# sumpower.net
KiCad netlist of a schematic drawn in Altium Designer
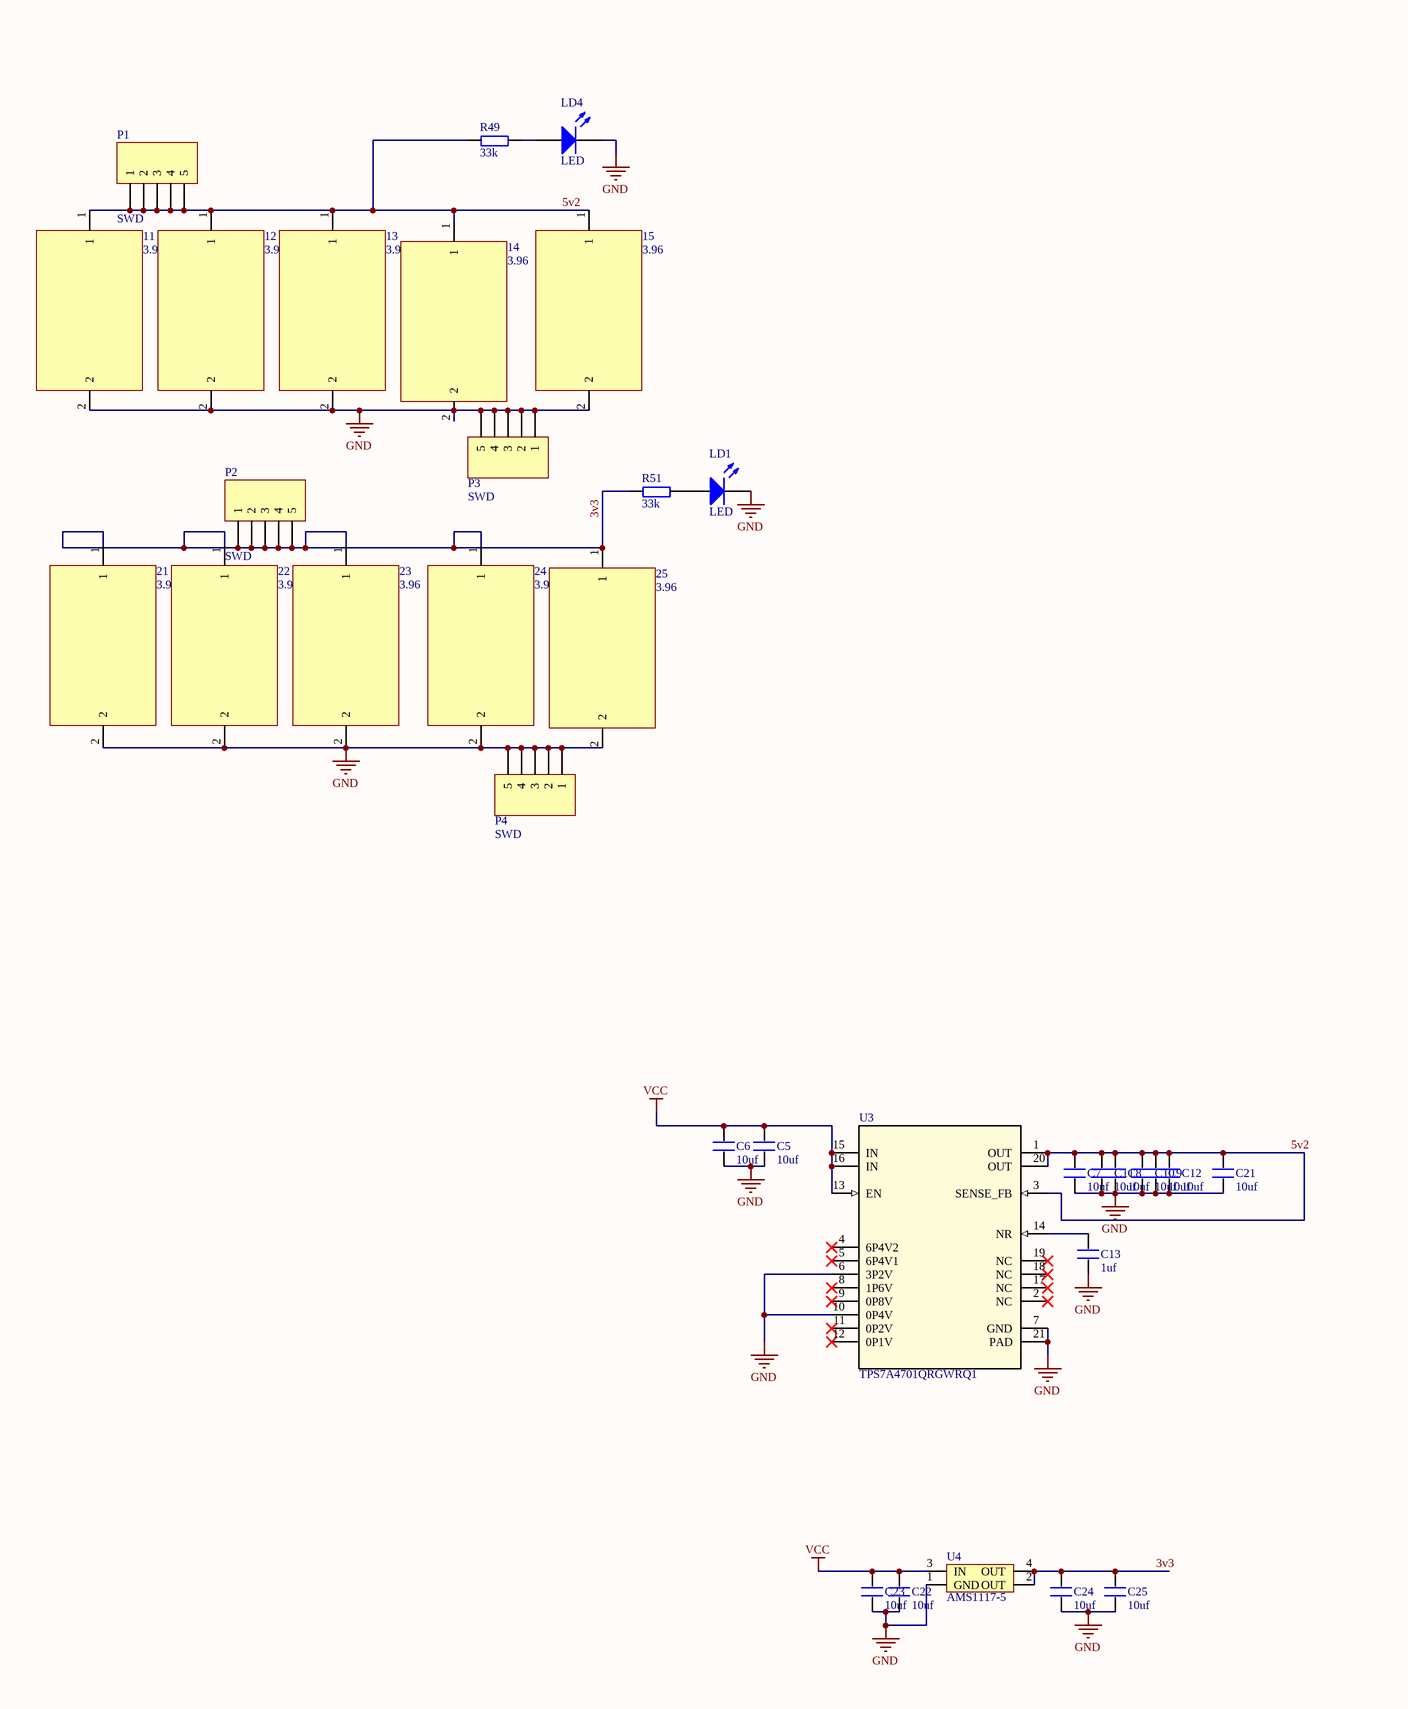
[diagram p0: sumpower.SchDoc, left]
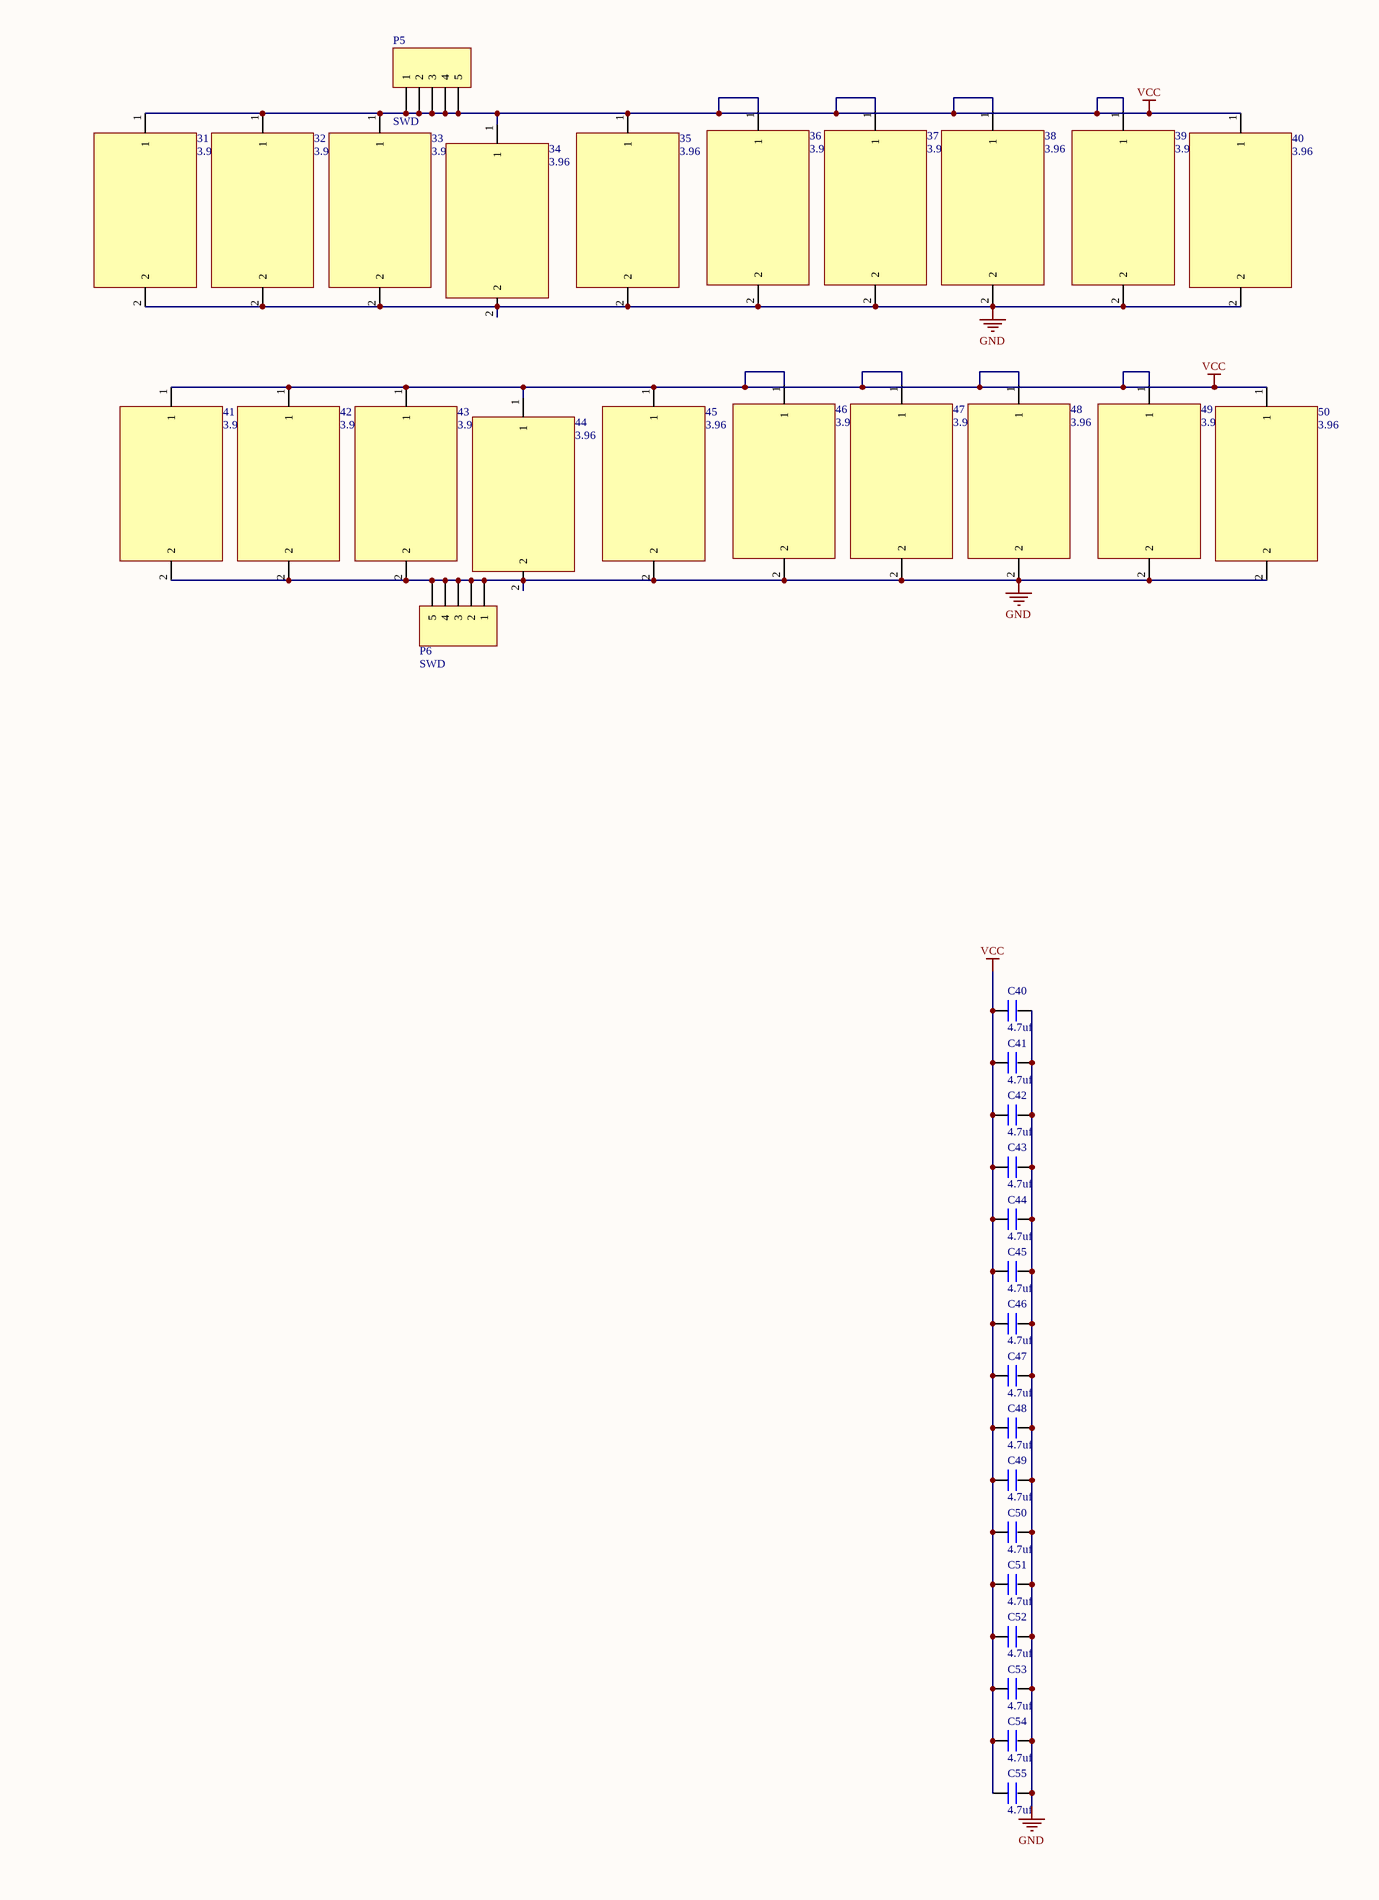
[diagram p1: sumpower.SchDoc, right]

(export (version "E")
  (design (tool "Eeschema 10.0.6"))
  (components
    (comp (ref "11") (value "3.96") (footprint "3.96") (libsource (lib "MYLIB") (part "3.96")))
    (comp (ref "12") (value "3.96") (footprint "3.96") (libsource (lib "MYLIB") (part "3.96")))
    (comp (ref "13") (value "3.96") (footprint "3.96") (libsource (lib "MYLIB") (part "3.96")))
    (comp (ref "14") (value "3.96") (footprint "3.96") (libsource (lib "MYLIB") (part "3.96")))
    (comp (ref "15") (value "3.96") (footprint "3.96") (libsource (lib "MYLIB") (part "3.96")))
    (comp (ref "21") (value "3.96") (footprint "3.96") (libsource (lib "MYLIB") (part "3.96")))
    (comp (ref "22") (value "3.96") (footprint "3.96") (libsource (lib "MYLIB") (part "3.96")))
    (comp (ref "23") (value "3.96") (footprint "3.96") (libsource (lib "MYLIB") (part "3.96")))
    (comp (ref "24") (value "3.96") (footprint "3.96") (libsource (lib "MYLIB") (part "3.96")))
    (comp (ref "25") (value "3.96") (footprint "3.96") (libsource (lib "MYLIB") (part "3.96")))
    (comp (ref "31") (value "3.96") (footprint "3.96") (libsource (lib "MYLIB") (part "3.96")))
    (comp (ref "32") (value "3.96") (footprint "3.96") (libsource (lib "MYLIB") (part "3.96")))
    (comp (ref "33") (value "3.96") (footprint "3.96") (libsource (lib "MYLIB") (part "3.96")))
    (comp (ref "34") (value "3.96") (footprint "3.96") (libsource (lib "MYLIB") (part "3.96")))
    (comp (ref "35") (value "3.96") (footprint "3.96") (libsource (lib "MYLIB") (part "3.96")))
    (comp (ref "36") (value "3.96") (footprint "3.96") (libsource (lib "MYLIB") (part "3.96")))
    (comp (ref "37") (value "3.96") (footprint "3.96") (libsource (lib "MYLIB") (part "3.96")))
    (comp (ref "38") (value "3.96") (footprint "3.96") (libsource (lib "MYLIB") (part "3.96")))
    (comp (ref "39") (value "3.96") (footprint "3.96") (libsource (lib "MYLIB") (part "3.96")))
    (comp (ref "40") (value "3.96") (footprint "3.96") (libsource (lib "MYLIB") (part "3.96")))
    (comp (ref "41") (value "3.96") (footprint "3.96") (libsource (lib "MYLIB") (part "3.96")))
    (comp (ref "42") (value "3.96") (footprint "3.96") (libsource (lib "MYLIB") (part "3.96")))
    (comp (ref "43") (value "3.96") (footprint "3.96") (libsource (lib "MYLIB") (part "3.96")))
    (comp (ref "44") (value "3.96") (footprint "3.96") (libsource (lib "MYLIB") (part "3.96")))
    (comp (ref "45") (value "3.96") (footprint "3.96") (libsource (lib "MYLIB") (part "3.96")))
    (comp (ref "46") (value "3.96") (footprint "3.96") (libsource (lib "MYLIB") (part "3.96")))
    (comp (ref "47") (value "3.96") (footprint "3.96") (libsource (lib "MYLIB") (part "3.96")))
    (comp (ref "48") (value "3.96") (footprint "3.96") (libsource (lib "MYLIB") (part "3.96")))
    (comp (ref "49") (value "3.96") (footprint "3.96") (libsource (lib "MYLIB") (part "3.96")))
    (comp (ref "50") (value "3.96") (footprint "3.96") (libsource (lib "MYLIB") (part "3.96")))
    (comp (ref "C5")
      (value "10uf")
      (footprint "0603C")
      (description "Capacitor")
      (libsource (lib "MYLIB") (part "C"))
    )
    (comp (ref "C6")
      (value "10uf")
      (footprint "0603C")
      (description "Capacitor")
      (libsource (lib "MYLIB") (part "C"))
    )
    (comp (ref "C7")
      (value "10uf")
      (footprint "0603C")
      (description "Capacitor")
      (libsource (lib "MYLIB") (part "C"))
    )
    (comp (ref "C8")
      (value "10uf")
      (footprint "0603C")
      (description "Capacitor")
      (libsource (lib "MYLIB") (part "C"))
    )
    (comp (ref "C9")
      (value "10uf")
      (footprint "0603C")
      (description "Capacitor")
      (libsource (lib "MYLIB") (part "C"))
    )
    (comp (ref "C10")
      (value "10uf")
      (footprint "0603C")
      (description "Capacitor")
      (libsource (lib "MYLIB") (part "C"))
    )
    (comp (ref "C11")
      (value "10uf")
      (footprint "0603C")
      (description "Capacitor")
      (libsource (lib "MYLIB") (part "C"))
    )
    (comp (ref "C12")
      (value "10uf")
      (footprint "0603C")
      (description "Capacitor")
      (libsource (lib "MYLIB") (part "C"))
    )
    (comp (ref "C13")
      (value "1uf")
      (footprint "0402")
      (description "Capacitor")
      (libsource (lib "MYLIB") (part "C"))
    )
    (comp (ref "C21")
      (value "10uf")
      (footprint "0603C")
      (description "Capacitor")
      (libsource (lib "MYLIB") (part "C"))
    )
    (comp (ref "C22")
      (value "10uf")
      (footprint "0603C")
      (description "Capacitor")
      (libsource (lib "MYLIB") (part "C"))
    )
    (comp (ref "C23")
      (value "10uf")
      (footprint "0603C")
      (description "Capacitor")
      (libsource (lib "MYLIB") (part "C"))
    )
    (comp (ref "C24")
      (value "10uf")
      (footprint "0603C")
      (description "Capacitor")
      (libsource (lib "MYLIB") (part "C"))
    )
    (comp (ref "C25")
      (value "10uf")
      (footprint "0603C")
      (description "Capacitor")
      (libsource (lib "MYLIB") (part "C"))
    )
    (comp (ref "C40")
      (value "4.7uf")
      (footprint "0603C")
      (description "Capacitor")
      (libsource (lib "MYLIB") (part "C"))
    )
    (comp (ref "C41")
      (value "4.7uf")
      (footprint "0603C")
      (description "Capacitor")
      (libsource (lib "MYLIB") (part "C"))
    )
    (comp (ref "C42")
      (value "4.7uf")
      (footprint "0603C")
      (description "Capacitor")
      (libsource (lib "MYLIB") (part "C"))
    )
    (comp (ref "C43")
      (value "4.7uf")
      (footprint "0603C")
      (description "Capacitor")
      (libsource (lib "MYLIB") (part "C"))
    )
    (comp (ref "C44")
      (value "4.7uf")
      (footprint "0603C")
      (description "Capacitor")
      (libsource (lib "MYLIB") (part "C"))
    )
    (comp (ref "C45")
      (value "4.7uf")
      (footprint "0603C")
      (description "Capacitor")
      (libsource (lib "MYLIB") (part "C"))
    )
    (comp (ref "C46")
      (value "4.7uf")
      (footprint "0603C")
      (description "Capacitor")
      (libsource (lib "MYLIB") (part "C"))
    )
    (comp (ref "C47")
      (value "4.7uf")
      (footprint "0603C")
      (description "Capacitor")
      (libsource (lib "MYLIB") (part "C"))
    )
    (comp (ref "C48")
      (value "4.7uf")
      (footprint "0603C")
      (description "Capacitor")
      (libsource (lib "MYLIB") (part "C"))
    )
    (comp (ref "C49")
      (value "4.7uf")
      (footprint "0603C")
      (description "Capacitor")
      (libsource (lib "MYLIB") (part "C"))
    )
    (comp (ref "C50")
      (value "4.7uf")
      (footprint "0603C")
      (description "Capacitor")
      (libsource (lib "MYLIB") (part "C"))
    )
    (comp (ref "C51")
      (value "4.7uf")
      (footprint "0603C")
      (description "Capacitor")
      (libsource (lib "MYLIB") (part "C"))
    )
    (comp (ref "C52")
      (value "4.7uf")
      (footprint "0603C")
      (description "Capacitor")
      (libsource (lib "MYLIB") (part "C"))
    )
    (comp (ref "C53")
      (value "4.7uf")
      (footprint "0603C")
      (description "Capacitor")
      (libsource (lib "MYLIB") (part "C"))
    )
    (comp (ref "C54")
      (value "4.7uf")
      (footprint "0603C")
      (description "Capacitor")
      (libsource (lib "MYLIB") (part "C"))
    )
    (comp (ref "C55")
      (value "4.7uf")
      (footprint "0603C")
      (description "Capacitor")
      (libsource (lib "MYLIB") (part "C"))
    )
    (comp (ref "LD1")
      (value "LED")
      (footprint "SMDLED")
      (description "Typical RED, GREEN, YELLOW, AMBER GaAs LED")
      (fields (field (name "PUBLISHER") "Altium Limited"))
      (libsource (lib "MYLIB") (part "LED"))
    )
    (comp (ref "LD4")
      (value "LED")
      (footprint "SMDLED")
      (description "Typical RED, GREEN, YELLOW, AMBER GaAs LED")
      (fields (field (name "PUBLISHER") "Altium Limited"))
      (libsource (lib "MYLIB") (part "LED"))
    )
    (comp (ref "P1")
      (value "SWD")
      (footprint "HDR1X5")
      (description "Header, 5-Pin")
      (fields (field (name "PUBLISHER") "Altium Limited"))
      (libsource (lib "") (part "Header 5_1"))
    )
    (comp (ref "P2")
      (value "SWD")
      (footprint "HDR1X5")
      (description "Header, 5-Pin")
      (fields (field (name "PUBLISHER") "Altium Limited"))
      (libsource (lib "") (part "Header 5_1"))
    )
    (comp (ref "P3")
      (value "SWD")
      (footprint "HDR1X5")
      (description "Header, 5-Pin")
      (fields (field (name "PUBLISHER") "Altium Limited"))
      (libsource (lib "MYLIB") (part "Header 5"))
    )
    (comp (ref "P4")
      (value "SWD")
      (footprint "HDR1X5")
      (description "Header, 5-Pin")
      (fields (field (name "PUBLISHER") "Altium Limited"))
      (libsource (lib "MYLIB") (part "Header 5"))
    )
    (comp (ref "P5")
      (value "SWD")
      (footprint "HDR1X5")
      (description "Header, 5-Pin")
      (fields (field (name "PUBLISHER") "Altium Limited"))
      (libsource (lib "") (part "Header 5_1"))
    )
    (comp (ref "P6")
      (value "SWD")
      (footprint "HDR1X5")
      (description "Header, 5-Pin")
      (fields (field (name "PUBLISHER") "Altium Limited"))
      (libsource (lib "MYLIB") (part "Header 5"))
    )
    (comp (ref "R49")
      (value "33k")
      (footprint "0603R")
      (description "Resistor")
      (libsource (lib "MYLIB") (part "Resistor"))
    )
    (comp (ref "R51")
      (value "33k")
      (footprint "0603R")
      (description "Resistor")
      (libsource (lib "MYLIB") (part "Resistor"))
    )
    (comp (ref "U3")
      (value "TPS7A4701QRGWRQ1")
      (footprint "RGW0020A")
      (description "No Description Available")
      (fields
        (field (name "MANUFACTURER") "Texas Instruments")
        (field (name "COPYRIGHT") "Copyright (C) 2018 Accelerated Designs. All rights reserved")
      )
      (libsource (lib "MYLIB") (part "TPS7A4701QRGWRQ1"))
    )
    (comp (ref "U4") (value "AMS1117-5") (footprint "AMS1117") (libsource (lib "MYLIB") (part "AMS1117")))
  )
  (nets
    (net (code "1") (name "/3v3") (class "Default")
      (node (ref "21") (pin "1") (pinfunction "1_1") (pintype "passive"))
      (node (ref "22") (pin "1") (pinfunction "1_1") (pintype "passive"))
      (node (ref "23") (pin "1") (pinfunction "1_1") (pintype "passive"))
      (node (ref "24") (pin "1") (pinfunction "1_1") (pintype "passive"))
      (node (ref "25") (pin "1") (pinfunction "1_1") (pintype "passive"))
      (node (ref "C24") (pin "2") (pintype "passive"))
      (node (ref "C25") (pin "2") (pintype "passive"))
      (node (ref "P2") (pin "1") (pinfunction "1_1") (pintype "passive"))
      (node (ref "P2") (pin "2") (pinfunction "2_2") (pintype "passive"))
      (node (ref "P2") (pin "3") (pinfunction "3_3") (pintype "passive"))
      (node (ref "P2") (pin "4") (pinfunction "4_4") (pintype "passive"))
      (node (ref "P2") (pin "5") (pinfunction "5_5") (pintype "passive"))
      (node (ref "R51") (pin "1") (pintype "passive"))
      (node (ref "U4") (pin "2") (pinfunction "OUT_2") (pintype "passive"))
      (node (ref "U4") (pin "4") (pinfunction "OUT_4") (pintype "passive"))
    )
    (net (code "2") (name "/5v2") (class "Default")
      (node (ref "11") (pin "1") (pinfunction "1_1") (pintype "passive"))
      (node (ref "12") (pin "1") (pinfunction "1_1") (pintype "passive"))
      (node (ref "13") (pin "1") (pinfunction "1_1") (pintype "passive"))
      (node (ref "14") (pin "1") (pinfunction "1_1") (pintype "passive"))
      (node (ref "15") (pin "1") (pinfunction "1_1") (pintype "passive"))
      (node (ref "C10") (pin "2") (pintype "passive"))
      (node (ref "C11") (pin "2") (pintype "passive"))
      (node (ref "C12") (pin "2") (pintype "passive"))
      (node (ref "C21") (pin "2") (pintype "passive"))
      (node (ref "C7") (pin "2") (pintype "passive"))
      (node (ref "C8") (pin "2") (pintype "passive"))
      (node (ref "C9") (pin "2") (pintype "passive"))
      (node (ref "P1") (pin "1") (pinfunction "1_1") (pintype "passive"))
      (node (ref "P1") (pin "2") (pinfunction "2_2") (pintype "passive"))
      (node (ref "P1") (pin "3") (pinfunction "3_3") (pintype "passive"))
      (node (ref "P1") (pin "4") (pinfunction "4_4") (pintype "passive"))
      (node (ref "P1") (pin "5") (pinfunction "5_5") (pintype "passive"))
      (node (ref "R49") (pin "1") (pintype "passive"))
      (node (ref "U3") (pin "1") (pinfunction "OUT_1") (pintype "power_in"))
      (node (ref "U3") (pin "20") (pinfunction "OUT_20") (pintype "power_in"))
      (node (ref "U3") (pin "3") (pinfunction "SENSE_FB_3") (pintype "input"))
    )
    (net (code "3") (name "GND") (class "Default")
      (node (ref "11") (pin "2") (pinfunction "2_2") (pintype "passive"))
      (node (ref "12") (pin "2") (pinfunction "2_2") (pintype "passive"))
      (node (ref "13") (pin "2") (pinfunction "2_2") (pintype "passive"))
      (node (ref "14") (pin "2") (pinfunction "2_2") (pintype "passive"))
      (node (ref "15") (pin "2") (pinfunction "2_2") (pintype "passive"))
      (node (ref "21") (pin "2") (pinfunction "2_2") (pintype "passive"))
      (node (ref "22") (pin "2") (pinfunction "2_2") (pintype "passive"))
      (node (ref "23") (pin "2") (pinfunction "2_2") (pintype "passive"))
      (node (ref "24") (pin "2") (pinfunction "2_2") (pintype "passive"))
      (node (ref "25") (pin "2") (pinfunction "2_2") (pintype "passive"))
      (node (ref "31") (pin "2") (pinfunction "2_2") (pintype "passive"))
      (node (ref "32") (pin "2") (pinfunction "2_2") (pintype "passive"))
      (node (ref "33") (pin "2") (pinfunction "2_2") (pintype "passive"))
      (node (ref "34") (pin "2") (pinfunction "2_2") (pintype "passive"))
      (node (ref "35") (pin "2") (pinfunction "2_2") (pintype "passive"))
      (node (ref "36") (pin "2") (pinfunction "2_2") (pintype "passive"))
      (node (ref "37") (pin "2") (pinfunction "2_2") (pintype "passive"))
      (node (ref "38") (pin "2") (pinfunction "2_2") (pintype "passive"))
      (node (ref "39") (pin "2") (pinfunction "2_2") (pintype "passive"))
      (node (ref "40") (pin "2") (pinfunction "2_2") (pintype "passive"))
      (node (ref "41") (pin "2") (pinfunction "2_2") (pintype "passive"))
      (node (ref "42") (pin "2") (pinfunction "2_2") (pintype "passive"))
      (node (ref "43") (pin "2") (pinfunction "2_2") (pintype "passive"))
      (node (ref "44") (pin "2") (pinfunction "2_2") (pintype "passive"))
      (node (ref "45") (pin "2") (pinfunction "2_2") (pintype "passive"))
      (node (ref "46") (pin "2") (pinfunction "2_2") (pintype "passive"))
      (node (ref "47") (pin "2") (pinfunction "2_2") (pintype "passive"))
      (node (ref "48") (pin "2") (pinfunction "2_2") (pintype "passive"))
      (node (ref "49") (pin "2") (pinfunction "2_2") (pintype "passive"))
      (node (ref "50") (pin "2") (pinfunction "2_2") (pintype "passive"))
      (node (ref "C10") (pin "1") (pintype "passive"))
      (node (ref "C11") (pin "1") (pintype "passive"))
      (node (ref "C12") (pin "1") (pintype "passive"))
      (node (ref "C13") (pin "1") (pintype "passive"))
      (node (ref "C21") (pin "1") (pintype "passive"))
      (node (ref "C22") (pin "1") (pintype "passive"))
      (node (ref "C23") (pin "1") (pintype "passive"))
      (node (ref "C24") (pin "1") (pintype "passive"))
      (node (ref "C25") (pin "1") (pintype "passive"))
      (node (ref "C40") (pin "2") (pintype "passive"))
      (node (ref "C41") (pin "2") (pintype "passive"))
      (node (ref "C42") (pin "2") (pintype "passive"))
      (node (ref "C43") (pin "2") (pintype "passive"))
      (node (ref "C44") (pin "2") (pintype "passive"))
      (node (ref "C45") (pin "2") (pintype "passive"))
      (node (ref "C46") (pin "2") (pintype "passive"))
      (node (ref "C47") (pin "2") (pintype "passive"))
      (node (ref "C48") (pin "2") (pintype "passive"))
      (node (ref "C49") (pin "2") (pintype "passive"))
      (node (ref "C5") (pin "1") (pintype "passive"))
      (node (ref "C50") (pin "2") (pintype "passive"))
      (node (ref "C51") (pin "2") (pintype "passive"))
      (node (ref "C52") (pin "2") (pintype "passive"))
      (node (ref "C53") (pin "2") (pintype "passive"))
      (node (ref "C54") (pin "2") (pintype "passive"))
      (node (ref "C55") (pin "2") (pintype "passive"))
      (node (ref "C6") (pin "1") (pintype "passive"))
      (node (ref "C7") (pin "1") (pintype "passive"))
      (node (ref "C8") (pin "1") (pintype "passive"))
      (node (ref "C9") (pin "1") (pintype "passive"))
      (node (ref "LD1") (pin "2") (pinfunction "K_2") (pintype "passive"))
      (node (ref "LD4") (pin "2") (pinfunction "K_2") (pintype "passive"))
      (node (ref "P3") (pin "1") (pinfunction "1_1") (pintype "passive"))
      (node (ref "P3") (pin "2") (pinfunction "2_2") (pintype "passive"))
      (node (ref "P3") (pin "3") (pinfunction "3_3") (pintype "passive"))
      (node (ref "P3") (pin "4") (pinfunction "4_4") (pintype "passive"))
      (node (ref "P3") (pin "5") (pinfunction "5_5") (pintype "passive"))
      (node (ref "P4") (pin "1") (pinfunction "1_1") (pintype "passive"))
      (node (ref "P4") (pin "2") (pinfunction "2_2") (pintype "passive"))
      (node (ref "P4") (pin "3") (pinfunction "3_3") (pintype "passive"))
      (node (ref "P4") (pin "4") (pinfunction "4_4") (pintype "passive"))
      (node (ref "P4") (pin "5") (pinfunction "5_5") (pintype "passive"))
      (node (ref "P6") (pin "1") (pinfunction "1_1") (pintype "passive"))
      (node (ref "P6") (pin "2") (pinfunction "2_2") (pintype "passive"))
      (node (ref "P6") (pin "3") (pinfunction "3_3") (pintype "passive"))
      (node (ref "P6") (pin "4") (pinfunction "4_4") (pintype "passive"))
      (node (ref "P6") (pin "5") (pinfunction "5_5") (pintype "passive"))
      (node (ref "U3") (pin "10") (pinfunction "0P4V_10") (pintype "passive"))
      (node (ref "U3") (pin "21") (pinfunction "PAD_21") (pintype "passive"))
      (node (ref "U3") (pin "6") (pinfunction "3P2V_6") (pintype "passive"))
      (node (ref "U3") (pin "7") (pinfunction "GND_7") (pintype "power_in"))
      (node (ref "U4") (pin "1") (pinfunction "GND_1") (pintype "passive"))
    )
    (net (code "4") (name "Net-(LD1-A)") (class "Default")
      (node (ref "LD1") (pin "1") (pinfunction "A_1") (pintype "passive"))
      (node (ref "R51") (pin "2") (pintype "passive"))
    )
    (net (code "5") (name "Net-(LD4-A)") (class "Default")
      (node (ref "LD4") (pin "1") (pinfunction "A_1") (pintype "passive"))
      (node (ref "R49") (pin "2") (pintype "passive"))
    )
    (net (code "6") (name "Net-(U3-NR)") (class "Default")
      (node (ref "C13") (pin "2") (pintype "passive"))
      (node (ref "U3") (pin "14") (pinfunction "NR_14") (pintype "input"))
    )
    (net (code "7") (name "VCC") (class "Default")
      (node (ref "31") (pin "1") (pinfunction "1_1") (pintype "passive"))
      (node (ref "32") (pin "1") (pinfunction "1_1") (pintype "passive"))
      (node (ref "33") (pin "1") (pinfunction "1_1") (pintype "passive"))
      (node (ref "34") (pin "1") (pinfunction "1_1") (pintype "passive"))
      (node (ref "35") (pin "1") (pinfunction "1_1") (pintype "passive"))
      (node (ref "36") (pin "1") (pinfunction "1_1") (pintype "passive"))
      (node (ref "37") (pin "1") (pinfunction "1_1") (pintype "passive"))
      (node (ref "38") (pin "1") (pinfunction "1_1") (pintype "passive"))
      (node (ref "39") (pin "1") (pinfunction "1_1") (pintype "passive"))
      (node (ref "40") (pin "1") (pinfunction "1_1") (pintype "passive"))
      (node (ref "41") (pin "1") (pinfunction "1_1") (pintype "passive"))
      (node (ref "42") (pin "1") (pinfunction "1_1") (pintype "passive"))
      (node (ref "43") (pin "1") (pinfunction "1_1") (pintype "passive"))
      (node (ref "44") (pin "1") (pinfunction "1_1") (pintype "passive"))
      (node (ref "45") (pin "1") (pinfunction "1_1") (pintype "passive"))
      (node (ref "46") (pin "1") (pinfunction "1_1") (pintype "passive"))
      (node (ref "47") (pin "1") (pinfunction "1_1") (pintype "passive"))
      (node (ref "48") (pin "1") (pinfunction "1_1") (pintype "passive"))
      (node (ref "49") (pin "1") (pinfunction "1_1") (pintype "passive"))
      (node (ref "50") (pin "1") (pinfunction "1_1") (pintype "passive"))
      (node (ref "C22") (pin "2") (pintype "passive"))
      (node (ref "C23") (pin "2") (pintype "passive"))
      (node (ref "C40") (pin "1") (pintype "passive"))
      (node (ref "C41") (pin "1") (pintype "passive"))
      (node (ref "C42") (pin "1") (pintype "passive"))
      (node (ref "C43") (pin "1") (pintype "passive"))
      (node (ref "C44") (pin "1") (pintype "passive"))
      (node (ref "C45") (pin "1") (pintype "passive"))
      (node (ref "C46") (pin "1") (pintype "passive"))
      (node (ref "C47") (pin "1") (pintype "passive"))
      (node (ref "C48") (pin "1") (pintype "passive"))
      (node (ref "C49") (pin "1") (pintype "passive"))
      (node (ref "C5") (pin "2") (pintype "passive"))
      (node (ref "C50") (pin "1") (pintype "passive"))
      (node (ref "C51") (pin "1") (pintype "passive"))
      (node (ref "C52") (pin "1") (pintype "passive"))
      (node (ref "C53") (pin "1") (pintype "passive"))
      (node (ref "C54") (pin "1") (pintype "passive"))
      (node (ref "C55") (pin "1") (pintype "passive"))
      (node (ref "C6") (pin "2") (pintype "passive"))
      (node (ref "P5") (pin "1") (pinfunction "1_1") (pintype "passive"))
      (node (ref "P5") (pin "2") (pinfunction "2_2") (pintype "passive"))
      (node (ref "P5") (pin "3") (pinfunction "3_3") (pintype "passive"))
      (node (ref "P5") (pin "4") (pinfunction "4_4") (pintype "passive"))
      (node (ref "P5") (pin "5") (pinfunction "5_5") (pintype "passive"))
      (node (ref "U3") (pin "13") (pinfunction "EN_13") (pintype "input"))
      (node (ref "U3") (pin "15") (pinfunction "IN_15") (pintype "power_in"))
      (node (ref "U3") (pin "16") (pinfunction "IN_16") (pintype "power_in"))
      (node (ref "U4") (pin "3") (pinfunction "IN_3") (pintype "passive"))
    )
    (net (code "8") (name "unconnected-(U3-0P1V-Pad12)") (class "Default")
      (node (ref "U3") (pin "12") (pinfunction "0P1V_12") (pintype "passive+no_connect"))
    )
    (net (code "9") (name "unconnected-(U3-0P2V-Pad11)") (class "Default")
      (node (ref "U3") (pin "11") (pinfunction "0P2V_11") (pintype "passive+no_connect"))
    )
    (net (code "10") (name "unconnected-(U3-0P8V-Pad9)") (class "Default")
      (node (ref "U3") (pin "9") (pinfunction "0P8V_9") (pintype "passive+no_connect"))
    )
    (net (code "11") (name "unconnected-(U3-1P6V-Pad8)") (class "Default")
      (node (ref "U3") (pin "8") (pinfunction "1P6V_8") (pintype "passive+no_connect"))
    )
    (net (code "12") (name "unconnected-(U3-6P4V1-Pad5)") (class "Default")
      (node (ref "U3") (pin "5") (pinfunction "6P4V1_5") (pintype "passive+no_connect"))
    )
    (net (code "13") (name "unconnected-(U3-6P4V2-Pad4)") (class "Default")
      (node (ref "U3") (pin "4") (pinfunction "6P4V2_4") (pintype "passive+no_connect"))
    )
    (net (code "14") (name "unconnected-(U3-NC-Pad2)") (class "Default")
      (node (ref "U3") (pin "2") (pinfunction "NC_2") (pintype "passive+no_connect"))
    )
    (net (code "15") (name "unconnected-(U3-NC-Pad17)") (class "Default")
      (node (ref "U3") (pin "17") (pinfunction "NC_17") (pintype "passive+no_connect"))
    )
    (net (code "16") (name "unconnected-(U3-NC-Pad18)") (class "Default")
      (node (ref "U3") (pin "18") (pinfunction "NC_18") (pintype "passive+no_connect"))
    )
    (net (code "17") (name "unconnected-(U3-NC-Pad19)") (class "Default")
      (node (ref "U3") (pin "19") (pinfunction "NC_19") (pintype "passive+no_connect"))
    )
  )
)
